# SCH_sentra_2026-03-12.net
KiCad netlist of a schematic drawn in EasyEDA
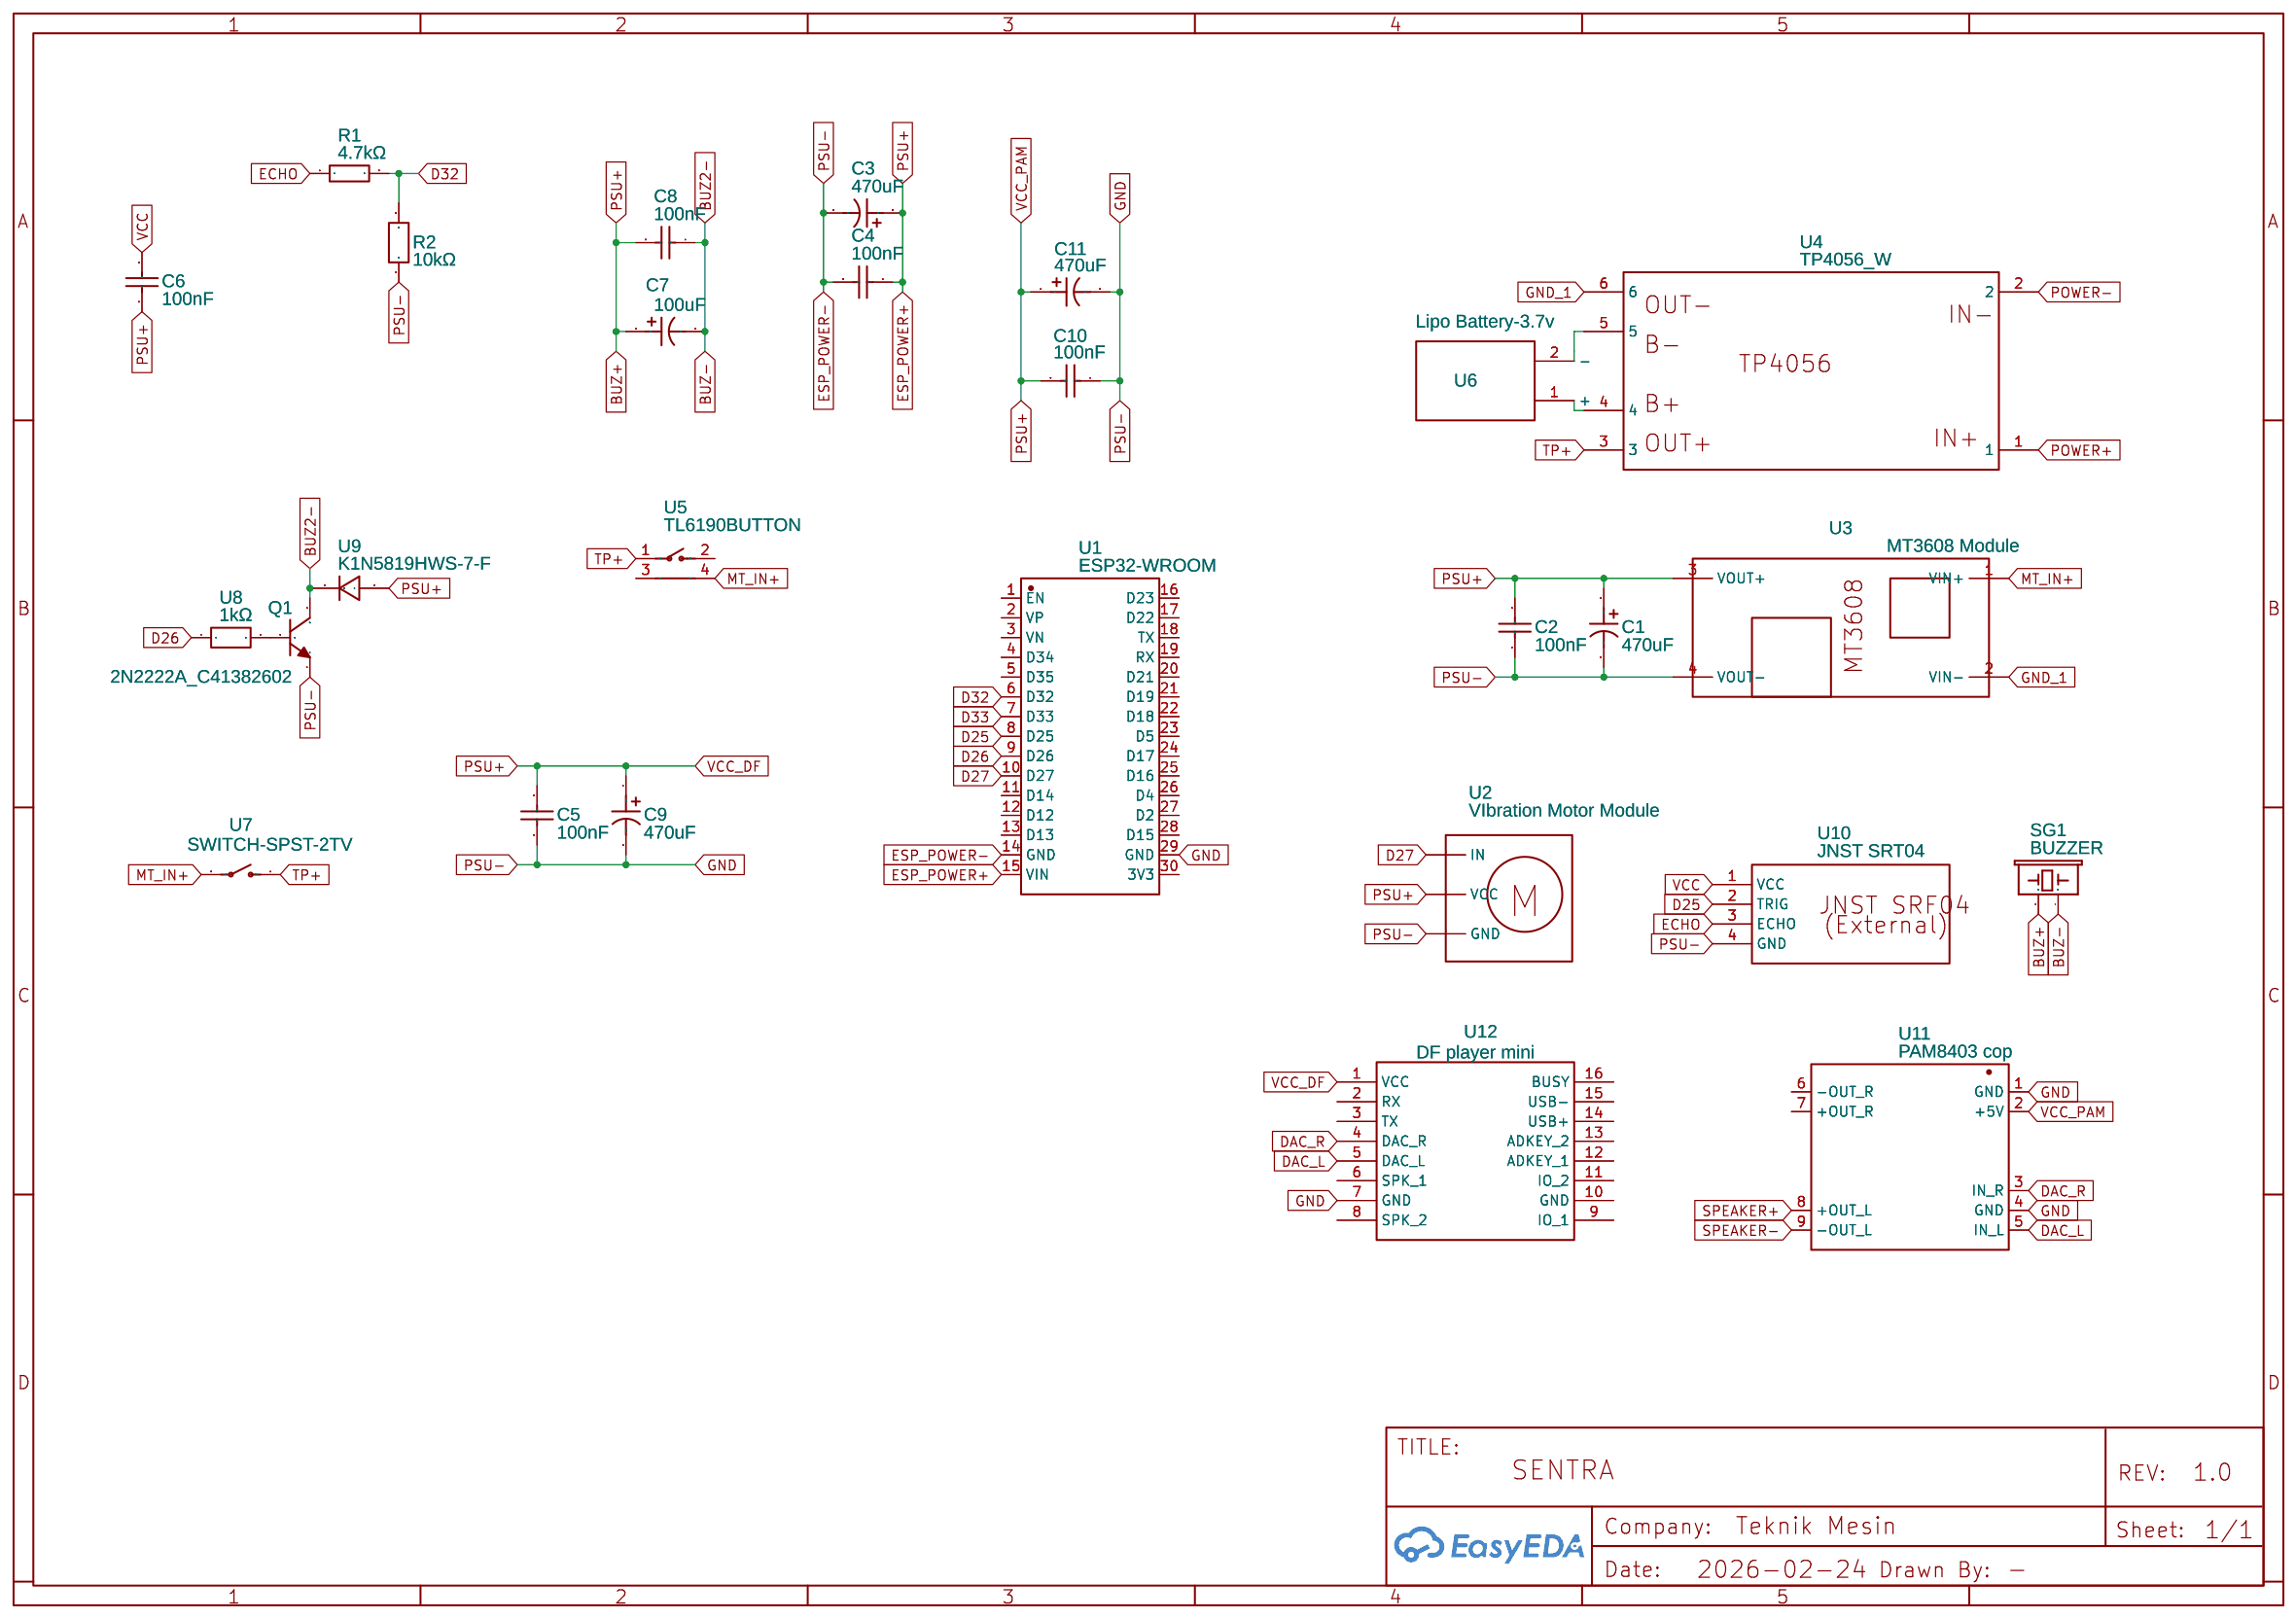
[diagram p0: schematic sheet]

(export (version "E")
  (design (tool "Eeschema 10.0.6"))
  (components
    (comp (ref "C1")
      (value "470uF")
      (fields (field (name "Manufacturer Part") "RYHV25V470UF8*10") (field (name "Manufacturer") "HONOR(荣誉)"))
      (libsource (lib "") (part "RYHV25V470UF8*10"))
    )
    (comp (ref "C2")
      (value "100nF")
      (fields
        (field (name "Manufacturer Part") "MPP104J2J1907128LC")
        (field (name "Manufacturer") "SRD(圣融达)")
      )
      (libsource (lib "") (part "MPP104J6190712LC"))
    )
    (comp (ref "C3")
      (value "470uF")
      (fields (field (name "Manufacturer Part") "RYHV25V470UF8*10") (field (name "Manufacturer") "HONOR(荣誉)"))
      (libsource (lib "") (part "RYHV25V470UF8*10_1"))
    )
    (comp (ref "C4")
      (value "100nF")
      (fields
        (field (name "Manufacturer Part") "MPP104J2J1907128LC")
        (field (name "Manufacturer") "SRD(圣融达)")
      )
      (libsource (lib "") (part "MPP104J6190712LC_2"))
    )
    (comp (ref "C5")
      (value "100nF")
      (fields
        (field (name "Manufacturer Part") "MPP104J2J1907128LC")
        (field (name "Manufacturer") "SRD(圣融达)")
      )
      (libsource (lib "") (part "MPP104J6190712LC"))
    )
    (comp (ref "C6")
      (value "100nF")
      (fields
        (field (name "Manufacturer Part") "MPP104J2J1907128LC")
        (field (name "Manufacturer") "SRD(圣融达)")
      )
      (libsource (lib "") (part "MPP104J6190712LC_1"))
    )
    (comp (ref "C7")
      (value "100uF")
      (fields
        (field (name "Manufacturer Part") "SHC450V100UF01EC3238")
        (field (name "Manufacturer") "KNSCHA(科尼盛)")
      )
      (libsource (lib "") (part "SHC450V100UF01EC3238"))
    )
    (comp (ref "C8")
      (value "100nF")
      (fields
        (field (name "Manufacturer Part") "MPP104J2J1907128LC")
        (field (name "Manufacturer") "SRD(圣融达)")
      )
      (libsource (lib "") (part "MPP104J6190712LC_2"))
    )
    (comp (ref "C9")
      (value "470uF")
      (fields (field (name "Manufacturer Part") "RYHV25V470UF8*10") (field (name "Manufacturer") "HONOR(荣誉)"))
      (libsource (lib "") (part "RYHV25V470UF8*10"))
    )
    (comp (ref "C10")
      (value "100nF")
      (fields
        (field (name "Manufacturer Part") "MPP104J2J1907128LC")
        (field (name "Manufacturer") "SRD(圣融达)")
      )
      (libsource (lib "") (part "MPP104J6190712LC_2"))
    )
    (comp (ref "C11")
      (value "470uF")
      (fields (field (name "Manufacturer Part") "RYHV25V470UF8*10") (field (name "Manufacturer") "HONOR(荣誉)"))
      (libsource (lib "") (part "RYHV25V470UF8*10_2"))
    )
    (comp (ref "Q1")
      (value "2N2222A_C41382602")
      (fields (field (name "Manufacturer Part") "2N2222A") (field (name "Manufacturer") "YFW(佑风微)"))
      (libsource (lib "") (part "2N2222A_C41382602"))
    )
    (comp (ref "R1")
      (value "4.7kΩ")
      (fields
        (field (name "Manufacturer Part") "MF1/2W-4.7KΩ±1% T")
        (field (name "Manufacturer") "CCO(千志电子)")
      )
      (libsource (lib "") (part "MF1/2W-4.7KΩ±1% T52"))
    )
    (comp (ref "R2")
      (value "10kΩ")
      (fields (field (name "Manufacturer Part") "TFSB10K0JE") (field (name "Manufacturer") "Ohmite"))
      (libsource (lib "") (part "TFSB10K0JE"))
    )
    (comp (ref "SG1") (value "BUZZER") (libsource (lib "") (part "BUZZER")))
    (comp (ref "U1")
      (value "ESP32-WROOM")
      (fields
        (field (name "Manufacturer Part") "ESP32 WROOM-32 ESP32-S")
        (field (name "Manufacturer") "ESPRESSIF(乐鑫)")
      )
      (libsource (lib "") (part "ESP32-WROOM"))
    )
    (comp (ref "U2") (value "VIbration Motor Module") (libsource (lib "") (part "VIbration Motor Module")))
    (comp (ref "U3") (value "MT3608 Module") (libsource (lib "") (part "MT3608 Module")))
    (comp (ref "U4") (value "TP4056_W") (libsource (lib "") (part "TP4056_W")))
    (comp (ref "U5")
      (value "TL6190BUTTON")
      (fields (field (name "Manufacturer") "E-Switch"))
      (libsource (lib "") (part "TL6190BUTTON"))
    )
    (comp (ref "U6") (value "Lipo Battery-3.7v") (libsource (lib "") (part "Lipo Battery-3.7v")))
    (comp (ref "U7") (value "SWITCH-SPST-2TV") (libsource (lib "") (part "SWITCH-SPST-2TV")))
    (comp (ref "U8")
      (value "1kΩ")
      (fields (field (name "Manufacturer Part") "SQP300JB-1K") (field (name "Manufacturer") "YAGEO(国巨)"))
      (libsource (lib "") (part "SQP300JB-1K"))
    )
    (comp (ref "U9")
      (value "K1N5819HWS-7-F")
      (fields (field (name "Manufacturer") "KUU"))
      (libsource (lib "") (part "K1N5819HWS-7-F"))
    )
    (comp (ref "U10") (value "JNST SRT04") (libsource (lib "") (part "HY-SRF05")))
    (comp (ref "U11")
      (value "PAM8403 cop")
      (fields (field (name "Manufacturer Part") "PAM8403DR") (field (name "Manufacturer") "DIODES"))
      (libsource (lib "") (part "PAM8403 cop"))
    )
    (comp (ref "U12") (value "DF player mini") (libsource (lib "") (part "DF player mini")))
  )
  (nets
    (net (code "1") (name "BUZ+") (class "Default")
      (node (ref "C1") (pin "1") (pinfunction "1_1") (pintype "input"))
      (node (ref "C10") (pin "2") (pinfunction "2_2") (pintype "input"))
      (node (ref "C11") (pin "1") (pinfunction "1_1") (pintype "input"))
      (node (ref "C2") (pin "2") (pinfunction "2_2") (pintype "input"))
      (node (ref "C3") (pin "1") (pinfunction "1_1") (pintype "input"))
      (node (ref "C4") (pin "1") (pinfunction "1_1") (pintype "input"))
      (node (ref "C5") (pin "2") (pinfunction "2_2") (pintype "input"))
      (node (ref "C6") (pin "2") (pinfunction "2_2") (pintype "input"))
      (node (ref "C7") (pin "1") (pinfunction "1_1") (pintype "input"))
      (node (ref "C8") (pin "2") (pinfunction "2_2") (pintype "input"))
      (node (ref "C9") (pin "1") (pinfunction "1_1") (pintype "input"))
      (node (ref "SG1") (pin "+") (pinfunction "1_+") (pintype "unspecified"))
      (node (ref "U1") (pin "15") (pinfunction "VIN_15") (pintype "unspecified"))
      (node (ref "U11") (pin "2") (pinfunction "+5V_2") (pintype "unspecified"))
      (node (ref "U12") (pin "1") (pinfunction "VCC_1") (pintype "unspecified"))
      (node (ref "U2") (pin "2") (pinfunction "VCC_2") (pintype "unspecified"))
      (node (ref "U3") (pin "3") (pinfunction "VOUT+_3") (pintype "unspecified"))
      (node (ref "U9") (pin "2") (pinfunction "A_2") (pintype "unspecified"))
    )
    (net (code "2") (name "BUZ-") (class "Default")
      (node (ref "C7") (pin "2") (pinfunction "2_2") (pintype "input"))
      (node (ref "C8") (pin "1") (pinfunction "1_1") (pintype "input"))
      (node (ref "Q1") (pin "3") (pinfunction "C_3") (pintype "unspecified"))
      (node (ref "SG1") (pin "-") (pinfunction "2_-") (pintype "unspecified"))
      (node (ref "U9") (pin "1") (pinfunction "C_1") (pintype "unspecified"))
    )
    (net (code "3") (name "D25") (class "Default")
      (node (ref "U1") (pin "8") (pinfunction "D25_8") (pintype "unspecified"))
      (node (ref "U10") (pin "2") (pinfunction "TRIG_2") (pintype "input"))
    )
    (net (code "4") (name "D26") (class "Default")
      (node (ref "U1") (pin "9") (pinfunction "D26_9") (pintype "unspecified"))
      (node (ref "U8") (pin "1") (pinfunction "1_1") (pintype "unspecified"))
    )
    (net (code "5") (name "D27") (class "Default")
      (node (ref "U1") (pin "10") (pinfunction "D27_10") (pintype "unspecified"))
      (node (ref "U2") (pin "1") (pinfunction "IN_1") (pintype "unspecified"))
    )
    (net (code "6") (name "D32") (class "Default")
      (node (ref "R1") (pin "2") (pinfunction "2_2") (pintype "unspecified"))
      (node (ref "R2") (pin "2") (pinfunction "2_2") (pintype "unspecified"))
      (node (ref "U1") (pin "6") (pinfunction "D32_6") (pintype "unspecified"))
    )
    (net (code "7") (name "D33") (class "Default")
      (node (ref "U1") (pin "7") (pinfunction "D33_7") (pintype "unspecified"))
    )
    (net (code "8") (name "DAC_L") (class "Default")
      (node (ref "U11") (pin "5") (pinfunction "IN_L_5") (pintype "unspecified"))
      (node (ref "U12") (pin "5") (pinfunction "DAC_L_5") (pintype "unspecified"))
    )
    (net (code "9") (name "DAC_R") (class "Default")
      (node (ref "U11") (pin "3") (pinfunction "IN_R_3") (pintype "unspecified"))
      (node (ref "U12") (pin "4") (pinfunction "DAC_R_4") (pintype "unspecified"))
    )
    (net (code "10") (name "ECHO") (class "Default")
      (node (ref "R1") (pin "1") (pinfunction "1_1") (pintype "unspecified"))
      (node (ref "U10") (pin "3") (pinfunction "ECHO_3") (pintype "output"))
    )
    (net (code "11") (name "ESP_POWER-") (class "Default")
      (node (ref "C1") (pin "2") (pinfunction "2_2") (pintype "input"))
      (node (ref "C10") (pin "1") (pinfunction "1_1") (pintype "input"))
      (node (ref "C11") (pin "2") (pinfunction "2_2") (pintype "input"))
      (node (ref "C2") (pin "1") (pinfunction "1_1") (pintype "input"))
      (node (ref "C3") (pin "2") (pinfunction "2_2") (pintype "input"))
      (node (ref "C4") (pin "2") (pinfunction "2_2") (pintype "input"))
      (node (ref "C5") (pin "1") (pinfunction "1_1") (pintype "input"))
      (node (ref "C9") (pin "2") (pinfunction "2_2") (pintype "input"))
      (node (ref "Q1") (pin "1") (pinfunction "E_1") (pintype "unspecified"))
      (node (ref "R2") (pin "1") (pinfunction "1_1") (pintype "unspecified"))
      (node (ref "U1") (pin "14") (pinfunction "GND_14") (pintype "unspecified"))
      (node (ref "U1") (pin "29") (pinfunction "GND_29") (pintype "unspecified"))
      (node (ref "U10") (pin "4") (pinfunction "GND_4") (pintype "passive"))
      (node (ref "U11") (pin "1") (pinfunction "GND_1") (pintype "unspecified"))
      (node (ref "U11") (pin "4") (pinfunction "GND_4") (pintype "unspecified"))
      (node (ref "U12") (pin "7") (pinfunction "GND_7") (pintype "unspecified"))
      (node (ref "U2") (pin "3") (pinfunction "GND_3") (pintype "unspecified"))
      (node (ref "U3") (pin "4") (pinfunction "VOUT-_4") (pintype "unspecified"))
    )
    (net (code "12") (name "GND_1") (class "Default")
      (node (ref "U3") (pin "2") (pinfunction "VIN-_2") (pintype "unspecified"))
      (node (ref "U4") (pin "6") (pinfunction "6_6") (pintype "unspecified"))
    )
    (net (code "13") (name "MT_IN+") (class "Default")
      (node (ref "U3") (pin "1") (pinfunction "VIN+_1") (pintype "unspecified"))
      (node (ref "U5") (pin "4") (pinfunction "4_4") (pintype "unspecified"))
      (node (ref "U7") (pin "2") (pinfunction "P_2") (pintype "unspecified"))
    )
    (net (code "14") (name "Net-(Q1-B)") (class "Default")
      (node (ref "Q1") (pin "2") (pinfunction "B_2") (pintype "unspecified"))
      (node (ref "U8") (pin "2") (pinfunction "2_2") (pintype "unspecified"))
    )
    (net (code "15") (name "POWER+") (class "Default")
      (node (ref "U4") (pin "1") (pinfunction "1_1") (pintype "unspecified"))
    )
    (net (code "16") (name "POWER-") (class "Default")
      (node (ref "U4") (pin "2") (pinfunction "2_2") (pintype "unspecified"))
    )
    (net (code "17") (name "SPEAKER+") (class "Default")
      (node (ref "U11") (pin "8") (pinfunction "+OUT_L_8") (pintype "unspecified"))
    )
    (net (code "18") (name "SPEAKER-") (class "Default")
      (node (ref "U11") (pin "9") (pinfunction "-OUT_L_9") (pintype "unspecified"))
    )
    (net (code "19") (name "TP+") (class "Default")
      (node (ref "U4") (pin "3") (pinfunction "3_3") (pintype "unspecified"))
      (node (ref "U5") (pin "1") (pinfunction "1_1") (pintype "unspecified"))
      (node (ref "U7") (pin "1") (pinfunction "O_1") (pintype "unspecified"))
    )
    (net (code "20") (name "VCC") (class "Default")
      (node (ref "C6") (pin "1") (pinfunction "1_1") (pintype "input"))
      (node (ref "U10") (pin "1") (pinfunction "VCC_1") (pintype "passive"))
    )
    (net (code "21") (name "unconnected-(U1-3V3-Pad30)") (class "Default")
      (node (ref "U1") (pin "30") (pinfunction "3V3_30") (pintype "unspecified"))
    )
    (net (code "22") (name "unconnected-(U1-D2-Pad27)") (class "Default")
      (node (ref "U1") (pin "27") (pinfunction "D2_27") (pintype "unspecified"))
    )
    (net (code "23") (name "unconnected-(U1-D4-Pad26)") (class "Default")
      (node (ref "U1") (pin "26") (pinfunction "D4_26") (pintype "unspecified"))
    )
    (net (code "24") (name "unconnected-(U1-D5-Pad23)") (class "Default")
      (node (ref "U1") (pin "23") (pinfunction "D5_23") (pintype "unspecified"))
    )
    (net (code "25") (name "unconnected-(U1-D12-Pad12)") (class "Default")
      (node (ref "U1") (pin "12") (pinfunction "D12_12") (pintype "unspecified"))
    )
    (net (code "26") (name "unconnected-(U1-D13-Pad13)") (class "Default")
      (node (ref "U1") (pin "13") (pinfunction "D13_13") (pintype "unspecified"))
    )
    (net (code "27") (name "unconnected-(U1-D14-Pad11)") (class "Default")
      (node (ref "U1") (pin "11") (pinfunction "D14_11") (pintype "unspecified"))
    )
    (net (code "28") (name "unconnected-(U1-D15-Pad28)") (class "Default")
      (node (ref "U1") (pin "28") (pinfunction "D15_28") (pintype "unspecified"))
    )
    (net (code "29") (name "unconnected-(U1-D16-Pad25)") (class "Default")
      (node (ref "U1") (pin "25") (pinfunction "D16_25") (pintype "unspecified"))
    )
    (net (code "30") (name "unconnected-(U1-D17-Pad24)") (class "Default")
      (node (ref "U1") (pin "24") (pinfunction "D17_24") (pintype "unspecified"))
    )
    (net (code "31") (name "unconnected-(U1-D18-Pad22)") (class "Default")
      (node (ref "U1") (pin "22") (pinfunction "D18_22") (pintype "unspecified"))
    )
    (net (code "32") (name "unconnected-(U1-D19-Pad21)") (class "Default")
      (node (ref "U1") (pin "21") (pinfunction "D19_21") (pintype "unspecified"))
    )
    (net (code "33") (name "unconnected-(U1-D21-Pad20)") (class "Default")
      (node (ref "U1") (pin "20") (pinfunction "D21_20") (pintype "unspecified"))
    )
    (net (code "34") (name "unconnected-(U1-D22-Pad17)") (class "Default")
      (node (ref "U1") (pin "17") (pinfunction "D22_17") (pintype "unspecified"))
    )
    (net (code "35") (name "unconnected-(U1-D23-Pad16)") (class "Default")
      (node (ref "U1") (pin "16") (pinfunction "D23_16") (pintype "unspecified"))
    )
    (net (code "36") (name "unconnected-(U1-D34-Pad4)") (class "Default")
      (node (ref "U1") (pin "4") (pinfunction "D34_4") (pintype "unspecified"))
    )
    (net (code "37") (name "unconnected-(U1-D35-Pad5)") (class "Default")
      (node (ref "U1") (pin "5") (pinfunction "D35_5") (pintype "unspecified"))
    )
    (net (code "38") (name "unconnected-(U1-EN-Pad1)") (class "Default")
      (node (ref "U1") (pin "1") (pinfunction "EN_1") (pintype "unspecified"))
    )
    (net (code "39") (name "unconnected-(U1-RX-Pad19)") (class "Default")
      (node (ref "U1") (pin "19") (pinfunction "RX_19") (pintype "unspecified"))
    )
    (net (code "40") (name "unconnected-(U1-TX-Pad18)") (class "Default")
      (node (ref "U1") (pin "18") (pinfunction "TX_18") (pintype "unspecified"))
    )
    (net (code "41") (name "unconnected-(U1-VN-Pad3)") (class "Default")
      (node (ref "U1") (pin "3") (pinfunction "VN_3") (pintype "unspecified"))
    )
    (net (code "42") (name "unconnected-(U1-VP-Pad2)") (class "Default")
      (node (ref "U1") (pin "2") (pinfunction "VP_2") (pintype "unspecified"))
    )
    (net (code "43") (name "unconnected-(U4-Pad4)") (class "Default")
      (node (ref "U4") (pin "4") (pinfunction "4_4") (pintype "unspecified"))
    )
    (net (code "44") (name "unconnected-(U4-Pad5)") (class "Default")
      (node (ref "U4") (pin "5") (pinfunction "5_5") (pintype "unspecified"))
    )
    (net (code "45") (name "unconnected-(U5-Pad2)") (class "Default")
      (node (ref "U5") (pin "2") (pinfunction "2_2") (pintype "unspecified"))
    )
    (net (code "46") (name "unconnected-(U5-Pad3)") (class "Default")
      (node (ref "U5") (pin "3") (pinfunction "3_3") (pintype "unspecified"))
    )
    (net (code "47") (name "unconnected-(U6-+-Pad1)") (class "Default")
      (node (ref "U6") (pin "1") (pinfunction "+_1") (pintype "unspecified"))
    )
    (net (code "48") (name "unconnected-(U6---Pad2)") (class "Default")
      (node (ref "U6") (pin "2") (pinfunction "-_2") (pintype "unspecified"))
    )
    (net (code "49") (name "unconnected-(U11-+OUT_R-Pad7)") (class "Default")
      (node (ref "U11") (pin "7") (pinfunction "+OUT_R_7") (pintype "unspecified"))
    )
    (net (code "50") (name "unconnected-(U11--OUT_R-Pad6)") (class "Default")
      (node (ref "U11") (pin "6") (pinfunction "-OUT_R_6") (pintype "unspecified"))
    )
    (net (code "51") (name "unconnected-(U12-ADKEY_1-Pad12)") (class "Default")
      (node (ref "U12") (pin "12") (pinfunction "ADKEY_1_12") (pintype "unspecified"))
    )
    (net (code "52") (name "unconnected-(U12-ADKEY_2-Pad13)") (class "Default")
      (node (ref "U12") (pin "13") (pinfunction "ADKEY_2_13") (pintype "unspecified"))
    )
    (net (code "53") (name "unconnected-(U12-BUSY-Pad16)") (class "Default")
      (node (ref "U12") (pin "16") (pinfunction "BUSY_16") (pintype "unspecified"))
    )
    (net (code "54") (name "unconnected-(U12-GND-Pad10)") (class "Default")
      (node (ref "U12") (pin "10") (pinfunction "GND_10") (pintype "unspecified"))
    )
    (net (code "55") (name "unconnected-(U12-IO_1-Pad9)") (class "Default")
      (node (ref "U12") (pin "9") (pinfunction "IO_1_9") (pintype "unspecified"))
    )
    (net (code "56") (name "unconnected-(U12-IO_2-Pad11)") (class "Default")
      (node (ref "U12") (pin "11") (pinfunction "IO_2_11") (pintype "unspecified"))
    )
    (net (code "57") (name "unconnected-(U12-RX-Pad2)") (class "Default")
      (node (ref "U12") (pin "2") (pinfunction "RX_2") (pintype "unspecified"))
    )
    (net (code "58") (name "unconnected-(U12-SPK_1-Pad6)") (class "Default")
      (node (ref "U12") (pin "6") (pinfunction "SPK_1_6") (pintype "unspecified"))
    )
    (net (code "59") (name "unconnected-(U12-SPK_2-Pad8)") (class "Default")
      (node (ref "U12") (pin "8") (pinfunction "SPK_2_8") (pintype "unspecified"))
    )
    (net (code "60") (name "unconnected-(U12-TX-Pad3)") (class "Default")
      (node (ref "U12") (pin "3") (pinfunction "TX_3") (pintype "unspecified"))
    )
    (net (code "61") (name "unconnected-(U12-USB+-Pad14)") (class "Default")
      (node (ref "U12") (pin "14") (pinfunction "USB+_14") (pintype "unspecified"))
    )
    (net (code "62") (name "unconnected-(U12-USB--Pad15)") (class "Default")
      (node (ref "U12") (pin "15") (pinfunction "USB-_15") (pintype "unspecified"))
    )
  )
)
